# Schematic_5V_7805.net
KiCad netlist of a schematic drawn in Altium Designer
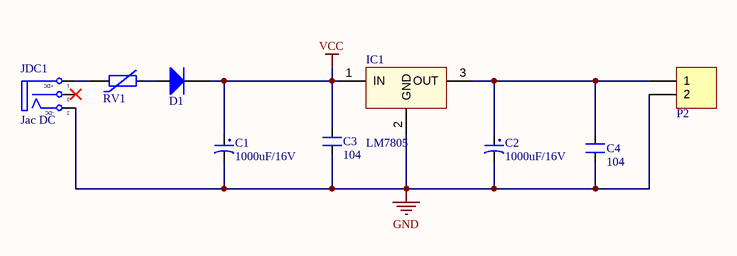
[diagram p0: Schematic_5V_7805.SchDoc]

(export (version "E")
  (design (tool "Eeschema 10.0.6"))
  (components
    (comp (ref "C1")
      (value "1000uF/16V")
      (footprint "CP1.5/3.4")
      (description "Cap 1000uF/16V - 220uF/50V")
      (libsource (lib "KhanhBK_SCH_Library_2") (part "CP4"))
    )
    (comp (ref "C2")
      (value "1000uF/16V")
      (footprint "CP1.5/3.4")
      (description "Cap 1000uF/16V - 220uF/50V")
      (libsource (lib "KhanhBK_SCH_Library_2") (part "CP4"))
    )
    (comp (ref "C3")
      (value "104")
      (footprint "CN2")
      (description "Cap np 104 => 105pF")
      (libsource (lib "KhanhBK_SCH_Library_2") (part "CN2"))
    )
    (comp (ref "C4")
      (value "104")
      (footprint "CN2")
      (description "Cap np 104 => 105pF")
      (libsource (lib "KhanhBK_SCH_Library_2") (part "CN2"))
    )
    (comp (ref "D1")
      (value "Diode")
      (footprint "D1A")
      (description "Default Diode")
      (libsource (lib "PIF_Library") (part "Diode"))
    )
    (comp (ref "IC1")
      (value "LM7805")
      (footprint "QTO-220")
      (description "On ap +, from + 5 to + 24VDC")
      (libsource (lib "KhanhBK_SCH_Library_2") (part "LM78xx"))
    )
    (comp (ref "JDC1")
      (value "Jac DC")
      (footprint "DC-IN")
      (description "Jac DC input")
      (libsource (lib "KhanhBK_SCH_Library_2") (part "DCIN"))
    )
    (comp (ref "P2")
      (value "Domino 2")
      (footprint "DOMINO 2- 5mm")
      (description "Domino, 2-Pin")
      (fields (field (name "PUBLISHER") "Altium Limited"))
      (libsource (lib "PIF_Library") (part "Domino 2"))
    )
    (comp (ref "RV1")
      (value "14VAC, 18VDC")
      (footprint "D9W4.5H12P0.8")
      (description "WE-VD Disk Varistor, THT, 14VAC, 18VDC, 2930pF")
      (fields
        (field (name "MANUFACTURER PART NUMBER") "820571406")
        (field (name "MANUFACTURER") "Wurth Elektronik")
      )
      (libsource (lib "Altium_WE-VD (rev23a)") (part "820571406"))
    )
  )
  (nets
    (net (code "1") (name "GND") (class "Default")
      (node (ref "C1") (pin "2") (pinfunction "2_2") (pintype "passive"))
      (node (ref "C2") (pin "2") (pinfunction "2_2") (pintype "passive"))
      (node (ref "C3") (pin "1") (pinfunction "1_1") (pintype "passive"))
      (node (ref "C4") (pin "1") (pinfunction "1_1") (pintype "passive"))
      (node (ref "IC1") (pin "2") (pinfunction "GND_2") (pintype "passive"))
      (node (ref "JDC1") (pin "2") (pinfunction "TN_2") (pintype "passive"))
      (node (ref "P2") (pin "2") (pinfunction "2_2") (pintype "passive"))
    )
    (net (code "2") (name "Net-(D1-A)") (class "Default")
      (node (ref "D1") (pin "1") (pinfunction "A_1") (pintype "passive"))
      (node (ref "RV1") (pin "2") (pinfunction "2_2") (pintype "passive"))
    )
    (net (code "3") (name "Net-(IC1-OUT)") (class "Default")
      (node (ref "C2") (pin "1") (pinfunction "1_1") (pintype "passive"))
      (node (ref "C4") (pin "2") (pinfunction "2_2") (pintype "passive"))
      (node (ref "IC1") (pin "3") (pinfunction "OUT_3") (pintype "passive"))
      (node (ref "P2") (pin "1") (pinfunction "1_1") (pintype "passive"))
    )
    (net (code "4") (name "Net-(JDC1-T)") (class "Default")
      (node (ref "JDC1") (pin "1") (pinfunction "T_1") (pintype "passive"))
      (node (ref "RV1") (pin "1") (pinfunction "1_1") (pintype "passive"))
    )
    (net (code "5") (name "VCC") (class "Default")
      (node (ref "C1") (pin "1") (pinfunction "1_1") (pintype "passive"))
      (node (ref "C3") (pin "2") (pinfunction "2_2") (pintype "passive"))
      (node (ref "D1") (pin "2") (pinfunction "K_2") (pintype "passive"))
      (node (ref "IC1") (pin "1") (pinfunction "IN_1") (pintype "passive"))
    )
    (net (code "6") (name "unconnected-(JDC1-S-Pad3)") (class "Default")
      (node (ref "JDC1") (pin "3") (pinfunction "S_3") (pintype "power_in+no_connect"))
    )
  )
)
